# Enclosure_100x68_BHCP.net
KiCad netlist of a schematic drawn in EAGLE
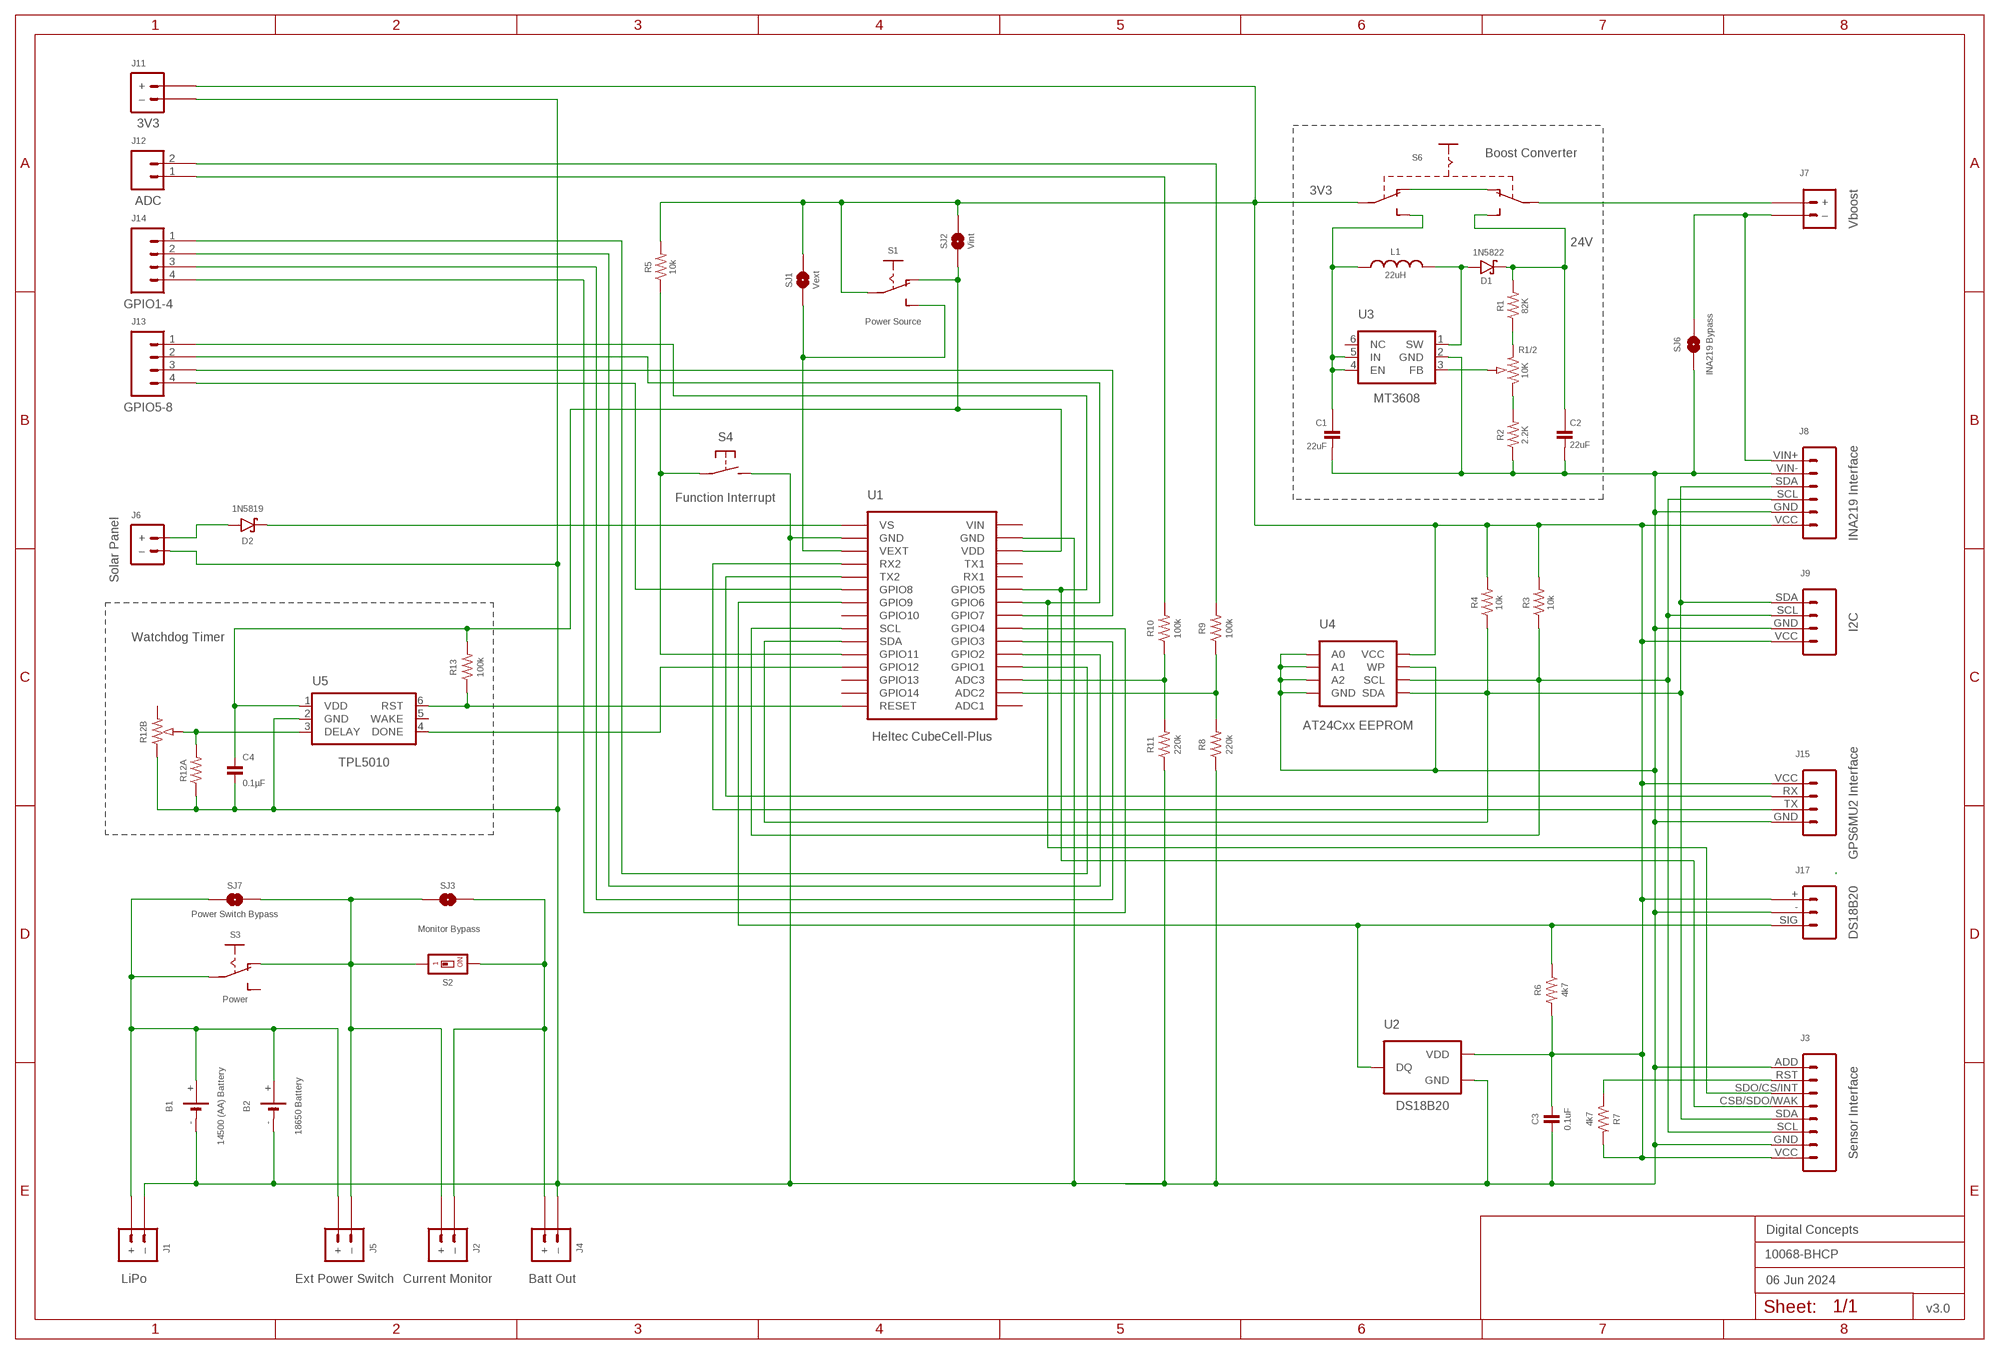
[diagram p0: schematic, sheet 1]

(export (version "E")
  (design (tool "Eeschema 10.0.6"))
  (components
    (comp (ref "B1")
      (value "14500 (AA) Battery")
      (footprint "eagle-import:BATTERY-14500")
      (libsource (lib "eagle-import") (part "BATTERY-HOLDER-14500(AA)"))
    )
    (comp (ref "B2")
      (value "18650 Battery")
      (footprint "eagle-import:BATTERY-18650")
      (libsource (lib "eagle-import") (part "BATTERY-HOLDER-18650"))
    )
    (comp (ref "C1")
      (value "22uF")
      (footprint "eagle-import:C1206")
      (libsource (lib "eagle-import") (part "CAPACITOR-1206"))
    )
    (comp (ref "C2")
      (value "22uF")
      (footprint "eagle-import:C1206")
      (libsource (lib "eagle-import") (part "CAPACITOR-1206"))
    )
    (comp (ref "C3")
      (value "0.1uF")
      (footprint "eagle-import:C0805")
      (libsource (lib "eagle-import") (part "CAPACITOR-0805"))
    )
    (comp (ref "C4")
      (value "0.1µF")
      (footprint "eagle-import:C0805")
      (libsource (lib "eagle-import") (part "CAPACITOR-0805"))
    )
    (comp (ref "D1")
      (value "1N5822")
      (footprint "eagle-import:DIODE_SMB")
      (libsource (lib "eagle-import") (part "DIODE-SCHOTTKY-1N5822"))
    )
    (comp (ref "D2")
      (value "1N5819")
      (footprint "eagle-import:SOD-123")
      (libsource (lib "eagle-import") (part "1N5819-SOD-123"))
    )
    (comp (ref "J1")
      (value "LiPo")
      (footprint "eagle-import:JST-PH2.0-2-HORIZONTAL-POWER")
      (libsource (lib "eagle-import") (part "JST-PH2.0-2-H-POWER"))
    )
    (comp (ref "J2")
      (value "Current Monitor")
      (footprint "eagle-import:JST-PH2.0-2-HORIZONTAL-POWER")
      (libsource (lib "eagle-import") (part "JST-PH2.0-2-H-POWER"))
    )
    (comp (ref "J3")
      (value "Sensor Interface")
      (footprint "eagle-import:CONN_08-SENSOR")
      (libsource (lib "eagle-import") (part "HEADER-1X8-SENSOR"))
    )
    (comp (ref "J4")
      (value "Batt Out")
      (footprint "eagle-import:JST-GH1.25-2-HORIZONTAL")
      (libsource (lib "eagle-import") (part "JST-GH1.25-2-HORIZONTAL-POWER"))
    )
    (comp (ref "J5")
      (value "Ext Power Switch")
      (footprint "eagle-import:JST-PH2.0-2-DUAL-POWER")
      (libsource (lib "eagle-import") (part "JST-PH2.0-2-DUAL-POWER{dblquote}"))
    )
    (comp (ref "J6")
      (value "Solar Panel")
      (footprint "eagle-import:JST-PH2.0-2-VERTICAL=POWER")
      (libsource (lib "eagle-import") (part "JST-PH2.0-2-VERTICAL"))
    )
    (comp (ref "J7")
      (value "Vboost")
      (footprint "eagle-import:JST-PH2.0-2-HORIZONTAL-POWER")
      (libsource (lib "eagle-import") (part "JST-PH2.0-2-H-POWER"))
    )
    (comp (ref "J8")
      (value "INA219 Interface")
      (footprint "eagle-import:CONN_06-INA219")
      (libsource (lib "eagle-import") (part "INA219-I2C-MODULE"))
    )
    (comp (ref "J9")
      (value "I2C")
      (footprint "eagle-import:JST-PH2.0-4-HORIZONTAL@1")
      (libsource (lib "eagle-import") (part "JST-PH2.0-I2C-MALE-HORIZONTAL"))
    )
    (comp (ref "J11")
      (value "3V3")
      (footprint "eagle-import:JST-PH2.0-2-HORIZONTAL-POWER")
      (libsource (lib "eagle-import") (part "JST-PH2.0-2-H-POWER"))
    )
    (comp (ref "J12")
      (value "ADC")
      (footprint "eagle-import:JST-PH2.0-2-HORIZONTAL")
      (libsource (lib "eagle-import") (part "JST-PH2.0-2-HORIZONTAL"))
    )
    (comp (ref "J13")
      (value "GPIO5-8")
      (footprint "eagle-import:JST-PH2.0-4-HORIZONTAL")
      (libsource (lib "eagle-import") (part "JST-PH2.0-4-HORIZONTAL"))
    )
    (comp (ref "J14")
      (value "GPIO1-4")
      (footprint "eagle-import:JST-PH2.0-4-HORIZONTAL")
      (libsource (lib "eagle-import") (part "JST-PH2.0-4-HORIZONTAL"))
    )
    (comp (ref "J15")
      (value "GPS6MU2 Interface")
      (footprint "eagle-import:CONN_04-GPS")
      (libsource (lib "eagle-import") (part "HEADER-1X4-GPS"))
    )
    (comp (ref "J17")
      (value "DS18B20")
      (footprint "eagle-import:JST-PH2.0-DS18B20-HORIZONTAL")
      (libsource (lib "eagle-import") (part "JST-PH2.0-3-HORIZONTAL-DS18B20"))
    )
    (comp (ref "L1")
      (value "22uH")
      (footprint "eagle-import:CDRH104R+6D28")
      (libsource (lib "eagle-import") (part "INDUCTOR-CDRH104R/6D28L5038P"))
    )
    (comp (ref "R1")
      (value "82K")
      (footprint "eagle-import:R0805")
      (libsource (lib "eagle-import") (part "RESISTORR0805"))
    )
    (comp (ref "R1/2")
      (value "10K")
      (footprint "eagle-import:RTRIM64P")
      (libsource (lib "eagle-import") (part "RESISTOR-TRIMM-BAOTER-H-US"))
    )
    (comp (ref "R2")
      (value "2.2K")
      (footprint "eagle-import:R0805")
      (libsource (lib "eagle-import") (part "RESISTORR0805"))
    )
    (comp (ref "R3")
      (value "10k")
      (footprint "eagle-import:R0805")
      (libsource (lib "eagle-import") (part "RESISTORR0805"))
    )
    (comp (ref "R4")
      (value "10k")
      (footprint "eagle-import:R0805")
      (libsource (lib "eagle-import") (part "RESISTORR0805"))
    )
    (comp (ref "R5")
      (value "10k")
      (footprint "eagle-import:R0805")
      (libsource (lib "eagle-import") (part "RESISTORR0805"))
    )
    (comp (ref "R6")
      (value "4k7")
      (footprint "eagle-import:R0805")
      (libsource (lib "eagle-import") (part "RESISTORR0805"))
    )
    (comp (ref "R7")
      (value "4k7")
      (footprint "eagle-import:R0805")
      (libsource (lib "eagle-import") (part "RESISTORR0805"))
    )
    (comp (ref "R8")
      (value "220k")
      (footprint "eagle-import:R0805")
      (libsource (lib "eagle-import") (part "RESISTORR0805"))
    )
    (comp (ref "R9")
      (value "100k")
      (footprint "eagle-import:R0805")
      (libsource (lib "eagle-import") (part "RESISTORR0805"))
    )
    (comp (ref "R10")
      (value "100k")
      (footprint "eagle-import:R0805")
      (libsource (lib "eagle-import") (part "RESISTORR0805"))
    )
    (comp (ref "R11")
      (value "220k")
      (footprint "eagle-import:R0805")
      (libsource (lib "eagle-import") (part "RESISTORR0805"))
    )
    (comp (ref "R12A")
      (value "RESISTORR0805")
      (footprint "eagle-import:R0805")
      (libsource (lib "eagle-import") (part "RESISTORR0805"))
    )
    (comp (ref "R12B")
      (value "RESISTOR-TRIMM-33-US")
      (footprint "eagle-import:RTRIM3_3")
      (libsource (lib "eagle-import") (part "RESISTOR-TRIMM-33-US"))
    )
    (comp (ref "R13")
      (value "100k")
      (footprint "eagle-import:R0805")
      (libsource (lib "eagle-import") (part "RESISTORR0805"))
    )
    (comp (ref "S1")
      (value "Power Source")
      (footprint "eagle-import:SWITCH-SPDT-SMT")
      (libsource (lib "eagle-import") (part "SWITCH-SLIDE-SPDT-SMT"))
    )
    (comp (ref "S2")
      (value "Monitor Bypass")
      (footprint "eagle-import:SMD-001")
      (libsource (lib "eagle-import") (part "SWITCH-DIP-SWS001"))
    )
    (comp (ref "S3")
      (value "Power")
      (footprint "eagle-import:SWITCH-SPDT-PTH")
      (libsource (lib "eagle-import") (part "SWITCH-SLIDE-SPDT-PTH"))
    )
    (comp (ref "S4")
      (value "Function Interrupt")
      (footprint "eagle-import:SWITCH-2-PAD")
      (libsource (lib "eagle-import") (part "SWITCH-MOMENTARY-2-PIN"))
    )
    (comp (ref "S6")
      (value "SWITCH-SLIDE-DPDT-PTH-S")
      (footprint "eagle-import:SWITCH-DPDT-PTH")
      (libsource (lib "eagle-import") (part "SWITCH-SLIDE-DPDT-PTH-S"))
    )
    (comp (ref "SJ1")
      (value "Vext")
      (footprint "eagle-import:SJ")
      (libsource (lib "eagle-import") (part "SJ"))
    )
    (comp (ref "SJ2")
      (value "Vint")
      (footprint "eagle-import:SJ-VIA-12")
      (libsource (lib "eagle-import") (part "SJ-V-12"))
    )
    (comp (ref "SJ3")
      (value "Monitor")
      (footprint "eagle-import:SJ")
      (libsource (lib "eagle-import") (part "SJ"))
    )
    (comp (ref "SJ6")
      (value "INA219 Bypass")
      (footprint "eagle-import:SJ")
      (libsource (lib "eagle-import") (part "SJ"))
    )
    (comp (ref "SJ7")
      (value "Power Switch Bypass")
      (footprint "eagle-import:SJ")
      (libsource (lib "eagle-import") (part "SJ"))
    )
    (comp (ref "U1")
      (value "Heltec CubeCell-Plus")
      (footprint "eagle-import:HELTEC-CUBECELL=PLUS-X")
      (libsource (lib "eagle-import") (part "HELTEC-CUBECELL-PLUS-X"))
    )
    (comp (ref "U2")
      (value "DS18B20")
      (footprint "eagle-import:TO-92")
      (fields (field (name "MF") "Maxim Integrated"))
      (libsource (lib "eagle-import") (part "THERMOMETER-DS18B20"))
    )
    (comp (ref "U3")
      (value "MT3608")
      (footprint "eagle-import:SOT-23-6")
      (libsource (lib "eagle-import") (part "MT3608"))
    )
    (comp (ref "U4")
      (value "AT24Cxx EEPROM")
      (footprint "eagle-import:SOP-8")
      (libsource (lib "eagle-import") (part "AT24CXX-EEPROM"))
    )
    (comp (ref "U5")
      (value "TPL5010")
      (footprint "eagle-import:SOT-23-6")
      (libsource (lib "eagle-import") (part "TPL5010DDCR"))
    )
  )
  (nets
    (net (code "1") (name "/VIN") (class "Default")
      (node (ref "U1") (pin "VIN") (pinfunction "VIN_VIN") (pintype "power_in"))
    )
    (net (code "2") (name "Net-(D2-PadA)") (class "Default")
      (node (ref "D2") (pin "A") (pinfunction "A_A") (pintype "passive"))
      (node (ref "J6") (pin "+") (pinfunction "+_+") (pintype "power_in"))
    )
    (net (code "3") (name "Net-(D2-PadC)") (class "Default")
      (node (ref "D2") (pin "C") (pinfunction "C_C") (pintype "passive"))
      (node (ref "U1") (pin "VS") (pinfunction "VS_VS") (pintype "power_in"))
    )
    (net (code "4") (name "Net-(J1-–)") (class "Default")
      (node (ref "B1") (pin "-") (pinfunction "-_-") (pintype "power_in"))
      (node (ref "B2") (pin "-") (pinfunction "-_-") (pintype "power_in"))
      (node (ref "C1") (pin "2") (pinfunction "2_2") (pintype "passive"))
      (node (ref "C2") (pin "2") (pinfunction "2_2") (pintype "passive"))
      (node (ref "C3") (pin "2") (pinfunction "2_2") (pintype "passive"))
      (node (ref "C4") (pin "2") (pinfunction "2_2") (pintype "passive"))
      (node (ref "J1") (pin "-") (pinfunction "–_-") (pintype "power_in"))
      (node (ref "J11") (pin "-") (pinfunction "–_-") (pintype "power_in"))
      (node (ref "J15") (pin "GND") (pinfunction "1_GND") (pintype "passive"))
      (node (ref "J17") (pin "-") (pinfunction "2_-") (pintype "passive"))
      (node (ref "J3") (pin "ADD") (pinfunction "8_ADD") (pintype "passive"))
      (node (ref "J3") (pin "GND") (pinfunction "2_GND") (pintype "passive"))
      (node (ref "J4") (pin "-") (pinfunction "–_-") (pintype "power_in"))
      (node (ref "J6") (pin "-") (pinfunction "–_-") (pintype "power_in"))
      (node (ref "J8") (pin "GND") (pinfunction "2_GND") (pintype "passive"))
      (node (ref "J8") (pin "VIN-") (pinfunction "5_VIN-") (pintype "passive"))
      (node (ref "J9") (pin "GND") (pinfunction "2_GND") (pintype "passive"))
      (node (ref "R11") (pin "1") (pinfunction "1_1") (pintype "passive"))
      (node (ref "R12A") (pin "1") (pinfunction "1_1") (pintype "passive"))
      (node (ref "R12B") (pin "1") (pinfunction "A_1") (pintype "passive"))
      (node (ref "R2") (pin "1") (pinfunction "1_1") (pintype "passive"))
      (node (ref "R8") (pin "1") (pinfunction "1_1") (pintype "passive"))
      (node (ref "S4") (pin "P$2") (pinfunction "S_P$2") (pintype "passive"))
      (node (ref "SJ6") (pin "1") (pinfunction "1_1") (pintype "passive"))
      (node (ref "U1") (pin "GND@14") (pinfunction "GND_GND@14") (pintype "power_in"))
      (node (ref "U1") (pin "GND@17") (pinfunction "GND_GND@17") (pintype "power_in"))
      (node (ref "U2") (pin "1") (pinfunction "GND_1") (pintype "power_in"))
      (node (ref "U3") (pin "2") (pinfunction "GND_2") (pintype "power_in"))
      (node (ref "U4") (pin "P$1") (pinfunction "A0_P$1") (pintype "bidirectional"))
      (node (ref "U4") (pin "P$2") (pinfunction "A1_P$2") (pintype "bidirectional"))
      (node (ref "U4") (pin "P$3") (pinfunction "A2_P$3") (pintype "bidirectional"))
      (node (ref "U4") (pin "P$4") (pinfunction "GND_P$4") (pintype "bidirectional"))
      (node (ref "U4") (pin "P$7") (pinfunction "WP_P$7") (pintype "bidirectional"))
      (node (ref "U5") (pin "2") (pinfunction "GND_2") (pintype "power_in"))
    )
    (net (code "5") (name "Net-(J2-–)") (class "Default")
      (node (ref "J2") (pin "-") (pinfunction "–_-") (pintype "power_in"))
      (node (ref "J4") (pin "+") (pinfunction "+_+") (pintype "power_in"))
      (node (ref "S2") (pin "2") (pinfunction "2_2") (pintype "passive"))
      (node (ref "SJ3") (pin "1") (pinfunction "1_1") (pintype "passive"))
    )
    (net (code "6") (name "Net-(J3-3)") (class "Default")
      (node (ref "J3") (pin "SCL") (pinfunction "3_SCL") (pintype "passive"))
      (node (ref "J8") (pin "SCL") (pinfunction "3_SCL") (pintype "passive"))
      (node (ref "J9") (pin "SCL") (pinfunction "3_SCL") (pintype "passive"))
      (node (ref "R3") (pin "1") (pinfunction "1_1") (pintype "passive"))
      (node (ref "U1") (pin "SCL") (pinfunction "SCL_SCL") (pintype "bidirectional"))
      (node (ref "U4") (pin "P$6") (pinfunction "SCL_P$6") (pintype "bidirectional"))
    )
    (net (code "7") (name "Net-(J3-4)") (class "Default")
      (node (ref "J3") (pin "SDA") (pinfunction "4_SDA") (pintype "passive"))
      (node (ref "J8") (pin "SDA") (pinfunction "4_SDA") (pintype "passive"))
      (node (ref "J9") (pin "SDA") (pinfunction "4_SDA") (pintype "passive"))
      (node (ref "R4") (pin "1") (pinfunction "1_1") (pintype "passive"))
      (node (ref "U1") (pin "SDA") (pinfunction "SDA_SDA") (pintype "bidirectional"))
      (node (ref "U4") (pin "P$5") (pinfunction "SDA_P$5") (pintype "bidirectional"))
    )
    (net (code "8") (name "Net-(J3-7)") (class "Default")
      (node (ref "J3") (pin "RST") (pinfunction "7_RST") (pintype "passive"))
      (node (ref "R7") (pin "1") (pinfunction "1_1") (pintype "passive"))
    )
    (net (code "9") (name "Net-(J5-–)") (class "Default")
      (node (ref "J2") (pin "+") (pinfunction "+_+") (pintype "power_in"))
      (node (ref "J5") (pin "-") (pinfunction "–_-") (pintype "power_in"))
      (node (ref "S2") (pin "1") (pinfunction "1_1") (pintype "passive"))
      (node (ref "S3") (pin "1") (pinfunction "O_1") (pintype "passive"))
      (node (ref "SJ3") (pin "2") (pinfunction "2_2") (pintype "passive"))
      (node (ref "SJ7") (pin "1") (pinfunction "1_1") (pintype "passive"))
    )
    (net (code "10") (name "Net-(J7-–)") (class "Default")
      (node (ref "J7") (pin "-") (pinfunction "–_-") (pintype "power_in"))
      (node (ref "J8") (pin "VIN+") (pinfunction "6_VIN+") (pintype "passive"))
      (node (ref "SJ6") (pin "2") (pinfunction "2_2") (pintype "passive"))
    )
    (net (code "11") (name "Net-(J12-Pad1)") (class "Default")
      (node (ref "J12") (pin "1") (pinfunction "1_1") (pintype "passive"))
      (node (ref "R10") (pin "2") (pinfunction "2_2") (pintype "passive"))
    )
    (net (code "12") (name "Net-(J12-Pad2)") (class "Default")
      (node (ref "J12") (pin "2") (pinfunction "2_2") (pintype "passive"))
      (node (ref "R9") (pin "2") (pinfunction "2_2") (pintype "passive"))
    )
    (net (code "13") (name "Net-(J13-1)") (class "Default")
      (node (ref "J13") (pin "4") (pinfunction "1_4") (pintype "passive"))
      (node (ref "U1") (pin "GPIO8") (pinfunction "GPIO8_GPIO8") (pintype "bidirectional"))
    )
    (net (code "14") (name "Net-(J13-2)") (class "Default")
      (node (ref "J13") (pin "3") (pinfunction "2_3") (pintype "passive"))
      (node (ref "U1") (pin "GPIO7") (pinfunction "GPIO7_GPIO7") (pintype "bidirectional"))
    )
    (net (code "15") (name "Net-(J13-3)") (class "Default")
      (node (ref "J13") (pin "2") (pinfunction "3_2") (pintype "passive"))
      (node (ref "J3") (pin "SDO/CS/INT") (pinfunction "6_SDO/CS/INT") (pintype "passive"))
      (node (ref "U1") (pin "GPIO6") (pinfunction "GPIO6_GPIO6") (pintype "bidirectional"))
    )
    (net (code "16") (name "Net-(J13-4)") (class "Default")
      (node (ref "J13") (pin "1") (pinfunction "4_1") (pintype "passive"))
      (node (ref "J3") (pin "CSB/SDO/WAK") (pinfunction "5_CSB/SDO/WAK") (pintype "passive"))
      (node (ref "U1") (pin "GPIO5") (pinfunction "GPIO5_GPIO5") (pintype "bidirectional"))
    )
    (net (code "17") (name "Net-(J14-1)") (class "Default")
      (node (ref "J14") (pin "4") (pinfunction "1_4") (pintype "passive"))
      (node (ref "U1") (pin "GPIO4") (pinfunction "GPIO4_GPIO4") (pintype "bidirectional"))
    )
    (net (code "18") (name "Net-(J14-2)") (class "Default")
      (node (ref "J14") (pin "3") (pinfunction "2_3") (pintype "passive"))
      (node (ref "U1") (pin "GPIO3") (pinfunction "GPIO3_GPIO3") (pintype "bidirectional"))
    )
    (net (code "19") (name "Net-(J14-3)") (class "Default")
      (node (ref "J14") (pin "2") (pinfunction "3_2") (pintype "passive"))
      (node (ref "U1") (pin "GPIO2") (pinfunction "GPIO2_GPIO2") (pintype "bidirectional"))
    )
    (net (code "20") (name "Net-(J14-4)") (class "Default")
      (node (ref "J14") (pin "1") (pinfunction "4_1") (pintype "passive"))
      (node (ref "U1") (pin "GPIO1") (pinfunction "GPIO1_GPIO1") (pintype "bidirectional"))
    )
    (net (code "21") (name "Net-(J15-2)") (class "Default")
      (node (ref "J15") (pin "TX") (pinfunction "2_TX") (pintype "passive"))
      (node (ref "U1") (pin "RX2") (pinfunction "RX2_RX2") (pintype "bidirectional"))
    )
    (net (code "22") (name "Net-(J15-3)") (class "Default")
      (node (ref "J15") (pin "RX") (pinfunction "3_RX") (pintype "passive"))
      (node (ref "U1") (pin "TX2") (pinfunction "TX2_TX2") (pintype "bidirectional"))
    )
    (net (code "23") (name "Net-(J15-4)") (class "Default")
      (node (ref "C3") (pin "1") (pinfunction "1_1") (pintype "passive"))
      (node (ref "J11") (pin "+") (pinfunction "+_+") (pintype "power_in"))
      (node (ref "J15") (pin "VCC") (pinfunction "4_VCC") (pintype "passive"))
      (node (ref "J17") (pin "+") (pinfunction "3_+") (pintype "passive"))
      (node (ref "J3") (pin "VCC") (pinfunction "1_VCC") (pintype "passive"))
      (node (ref "J8") (pin "VCC") (pinfunction "1_VCC") (pintype "passive"))
      (node (ref "J9") (pin "VCC") (pinfunction "1_VCC") (pintype "passive"))
      (node (ref "R3") (pin "2") (pinfunction "2_2") (pintype "passive"))
      (node (ref "R4") (pin "2") (pinfunction "2_2") (pintype "passive"))
      (node (ref "R5") (pin "2") (pinfunction "2_2") (pintype "passive"))
      (node (ref "R6") (pin "2") (pinfunction "2_2") (pintype "passive"))
      (node (ref "R7") (pin "2") (pinfunction "2_2") (pintype "passive"))
      (node (ref "S1") (pin "2") (pinfunction "P_2") (pintype "passive"))
      (node (ref "S6") (pin "P$5") (pinfunction "P2_P$5") (pintype "passive"))
      (node (ref "SJ1") (pin "2") (pinfunction "2_2") (pintype "passive"))
      (node (ref "SJ2") (pin "2") (pinfunction "2_2") (pintype "passive"))
      (node (ref "SJ2") (pin "2@V") (pinfunction "2_2@V") (pintype "passive"))
      (node (ref "U2") (pin "3") (pinfunction "VDD_3") (pintype "power_in"))
      (node (ref "U4") (pin "P$8") (pinfunction "VCC_P$8") (pintype "bidirectional"))
    )
    (net (code "24") (name "Net-(J17-1)") (class "Default")
      (node (ref "J17") (pin "SIG") (pinfunction "1_SIG") (pintype "passive"))
      (node (ref "R6") (pin "1") (pinfunction "1_1") (pintype "passive"))
      (node (ref "U1") (pin "GPIO9") (pinfunction "GPIO9_GPIO9") (pintype "bidirectional"))
      (node (ref "U2") (pin "2") (pinfunction "DQ_2") (pintype "bidirectional"))
    )
    (net (code "25") (name "Net-(R1/2-A)") (class "Default")
      (node (ref "R1/2") (pin "1") (pinfunction "A_1") (pintype "passive"))
      (node (ref "R2") (pin "2") (pinfunction "2_2") (pintype "passive"))
    )
    (net (code "26") (name "Net-(R1/2-E)") (class "Default")
      (node (ref "R1") (pin "1") (pinfunction "1_1") (pintype "passive"))
      (node (ref "R1/2") (pin "3") (pinfunction "E_3") (pintype "passive"))
    )
    (net (code "27") (name "Net-(R1/2-S)") (class "Default")
      (node (ref "R1/2") (pin "2") (pinfunction "S_2") (pintype "passive"))
      (node (ref "U3") (pin "3") (pinfunction "FB_3") (pintype "input"))
    )
    (net (code "28") (name "Net-(R8-Pad2)") (class "Default")
      (node (ref "R8") (pin "2") (pinfunction "2_2") (pintype "passive"))
      (node (ref "R9") (pin "1") (pinfunction "1_1") (pintype "passive"))
      (node (ref "U1") (pin "ADC2") (pinfunction "ADC2_ADC2") (pintype "bidirectional"))
    )
    (net (code "29") (name "Net-(R10-Pad1)") (class "Default")
      (node (ref "R10") (pin "1") (pinfunction "1_1") (pintype "passive"))
      (node (ref "R11") (pin "2") (pinfunction "2_2") (pintype "passive"))
      (node (ref "U1") (pin "ADC3") (pinfunction "ADC3_ADC3") (pintype "bidirectional"))
    )
    (net (code "30") (name "Net-(R12B-S)") (class "Default")
      (node (ref "R12A") (pin "2") (pinfunction "2_2") (pintype "passive"))
      (node (ref "R12B") (pin "2") (pinfunction "S_2") (pintype "passive"))
      (node (ref "U5") (pin "3") (pinfunction "DELAY_3") (pintype "input"))
    )
    (net (code "31") (name "Net-(S1-O)") (class "Default")
      (node (ref "C4") (pin "1") (pinfunction "1_1") (pintype "passive"))
      (node (ref "R13") (pin "2") (pinfunction "2_2") (pintype "passive"))
      (node (ref "S1") (pin "1") (pinfunction "O_1") (pintype "passive"))
      (node (ref "SJ2") (pin "1") (pinfunction "1_1") (pintype "passive"))
      (node (ref "SJ2") (pin "1@V") (pinfunction "1_1@V") (pintype "passive"))
      (node (ref "U1") (pin "VDD") (pinfunction "VDD_VDD") (pintype "power_in"))
      (node (ref "U5") (pin "1") (pinfunction "VDD_1") (pintype "power_in"))
    )
    (net (code "32") (name "Net-(S1-S)") (class "Default")
      (node (ref "S1") (pin "3") (pinfunction "S_3") (pintype "passive"))
      (node (ref "SJ1") (pin "1") (pinfunction "1_1") (pintype "passive"))
      (node (ref "U1") (pin "VEXT") (pinfunction "VEXT_VEXT") (pintype "power_in"))
    )
    (net (code "33") (name "Net-(S3-P)") (class "Default")
      (node (ref "B1") (pin "+") (pinfunction "+_+") (pintype "power_in"))
      (node (ref "B2") (pin "+") (pinfunction "+_+") (pintype "power_in"))
      (node (ref "J1") (pin "+") (pinfunction "+_+") (pintype "power_in"))
      (node (ref "J5") (pin "+") (pinfunction "+_+") (pintype "power_in"))
      (node (ref "S3") (pin "2") (pinfunction "P_2") (pintype "passive"))
      (node (ref "SJ7") (pin "2") (pinfunction "2_2") (pintype "passive"))
    )
    (net (code "34") (name "Net-(S4-P)") (class "Default")
      (node (ref "R5") (pin "1") (pinfunction "1_1") (pintype "passive"))
      (node (ref "S4") (pin "P$1") (pinfunction "P_P$1") (pintype "passive"))
      (node (ref "U1") (pin "GPIO11") (pinfunction "GPIO11_GPIO11") (pintype "bidirectional"))
    )
    (net (code "35") (name "Net-(S6-O1)") (class "Default")
      (node (ref "S6") (pin "P$1") (pinfunction "O1_P$1") (pintype "passive"))
      (node (ref "S6") (pin "P$4") (pinfunction "O2_P$4") (pintype "passive"))
    )
    (net (code "36") (name "Net-(S6-P1)") (class "Default")
      (node (ref "J7") (pin "+") (pinfunction "+_+") (pintype "power_in"))
      (node (ref "S6") (pin "P$2") (pinfunction "P1_P$2") (pintype "passive"))
    )
    (net (code "37") (name "Net-(S6-S1)") (class "Default")
      (node (ref "C2") (pin "1") (pinfunction "1_1") (pintype "passive"))
      (node (ref "D1") (pin "C") (pinfunction "C_C") (pintype "passive"))
      (node (ref "R1") (pin "2") (pinfunction "2_2") (pintype "passive"))
      (node (ref "S6") (pin "P$3") (pinfunction "S1_P$3") (pintype "passive"))
    )
    (net (code "38") (name "Net-(S6-S2)") (class "Default")
      (node (ref "C1") (pin "1") (pinfunction "1_1") (pintype "passive"))
      (node (ref "L1") (pin "2") (pinfunction "2_2") (pintype "passive"))
      (node (ref "S6") (pin "P$6") (pinfunction "S2_P$6") (pintype "passive"))
      (node (ref "U3") (pin "4") (pinfunction "EN_4") (pintype "input"))
      (node (ref "U3") (pin "5") (pinfunction "IN_5") (pintype "power_in"))
    )
    (net (code "39") (name "Net-(U1-RESET)") (class "Default")
      (node (ref "R13") (pin "1") (pinfunction "1_1") (pintype "passive"))
      (node (ref "U1") (pin "RST") (pinfunction "RESET_RST") (pintype "bidirectional"))
      (node (ref "U5") (pin "6") (pinfunction "RST_6") (pintype "output"))
    )
    (net (code "40") (name "Net-(U3-SW)") (class "Default")
      (node (ref "D1") (pin "A") (pinfunction "A_A") (pintype "passive"))
      (node (ref "L1") (pin "1") (pinfunction "1_1") (pintype "passive"))
      (node (ref "U3") (pin "1") (pinfunction "SW_1") (pintype "power_in"))
    )
    (net (code "41") (name "Net-(U5-DONE)") (class "Default")
      (node (ref "U1") (pin "GPIO12") (pinfunction "GPIO12_GPIO12") (pintype "bidirectional"))
      (node (ref "U5") (pin "4") (pinfunction "DONE_4") (pintype "input"))
    )
    (net (code "42") (name "unconnected-(R12B-E-Pad3)") (class "Default")
      (node (ref "R12B") (pin "3") (pinfunction "E_3") (pintype "passive"))
    )
    (net (code "43") (name "unconnected-(S3-S-Pad3)") (class "Default")
      (node (ref "S3") (pin "3") (pinfunction "S_3") (pintype "passive"))
    )
    (net (code "44") (name "unconnected-(U1-PadADC1)") (class "Default")
      (node (ref "U1") (pin "ADC1") (pinfunction "ADC1_ADC1") (pintype "bidirectional"))
    )
    (net (code "45") (name "unconnected-(U1-PadGPIO10)") (class "Default")
      (node (ref "U1") (pin "GPIO10") (pinfunction "GPIO10_GPIO10") (pintype "bidirectional"))
    )
    (net (code "46") (name "unconnected-(U1-PadGPIO13)") (class "Default")
      (node (ref "U1") (pin "GPIO13") (pinfunction "GPIO13_GPIO13") (pintype "bidirectional"))
    )
    (net (code "47") (name "unconnected-(U1-PadGPIO14)") (class "Default")
      (node (ref "U1") (pin "GPIO14") (pinfunction "GPIO14_GPIO14") (pintype "bidirectional"))
    )
    (net (code "48") (name "unconnected-(U1-PadRX1)") (class "Default")
      (node (ref "U1") (pin "RX1") (pinfunction "RX1_RX1") (pintype "bidirectional"))
    )
    (net (code "49") (name "unconnected-(U1-PadTX1)") (class "Default")
      (node (ref "U1") (pin "TX1") (pinfunction "TX1_TX1") (pintype "bidirectional"))
    )
    (net (code "50") (name "unconnected-(U3-NC-Pad6)") (class "Default")
      (node (ref "U3") (pin "6") (pinfunction "NC_6") (pintype "no_connect"))
    )
    (net (code "51") (name "unconnected-(U5-WAKE-Pad5)") (class "Default")
      (node (ref "U5") (pin "5") (pinfunction "WAKE_5") (pintype "output"))
    )
  )
)
